# bno08x_module.net
KiCad netlist of a schematic drawn in Altium Designer
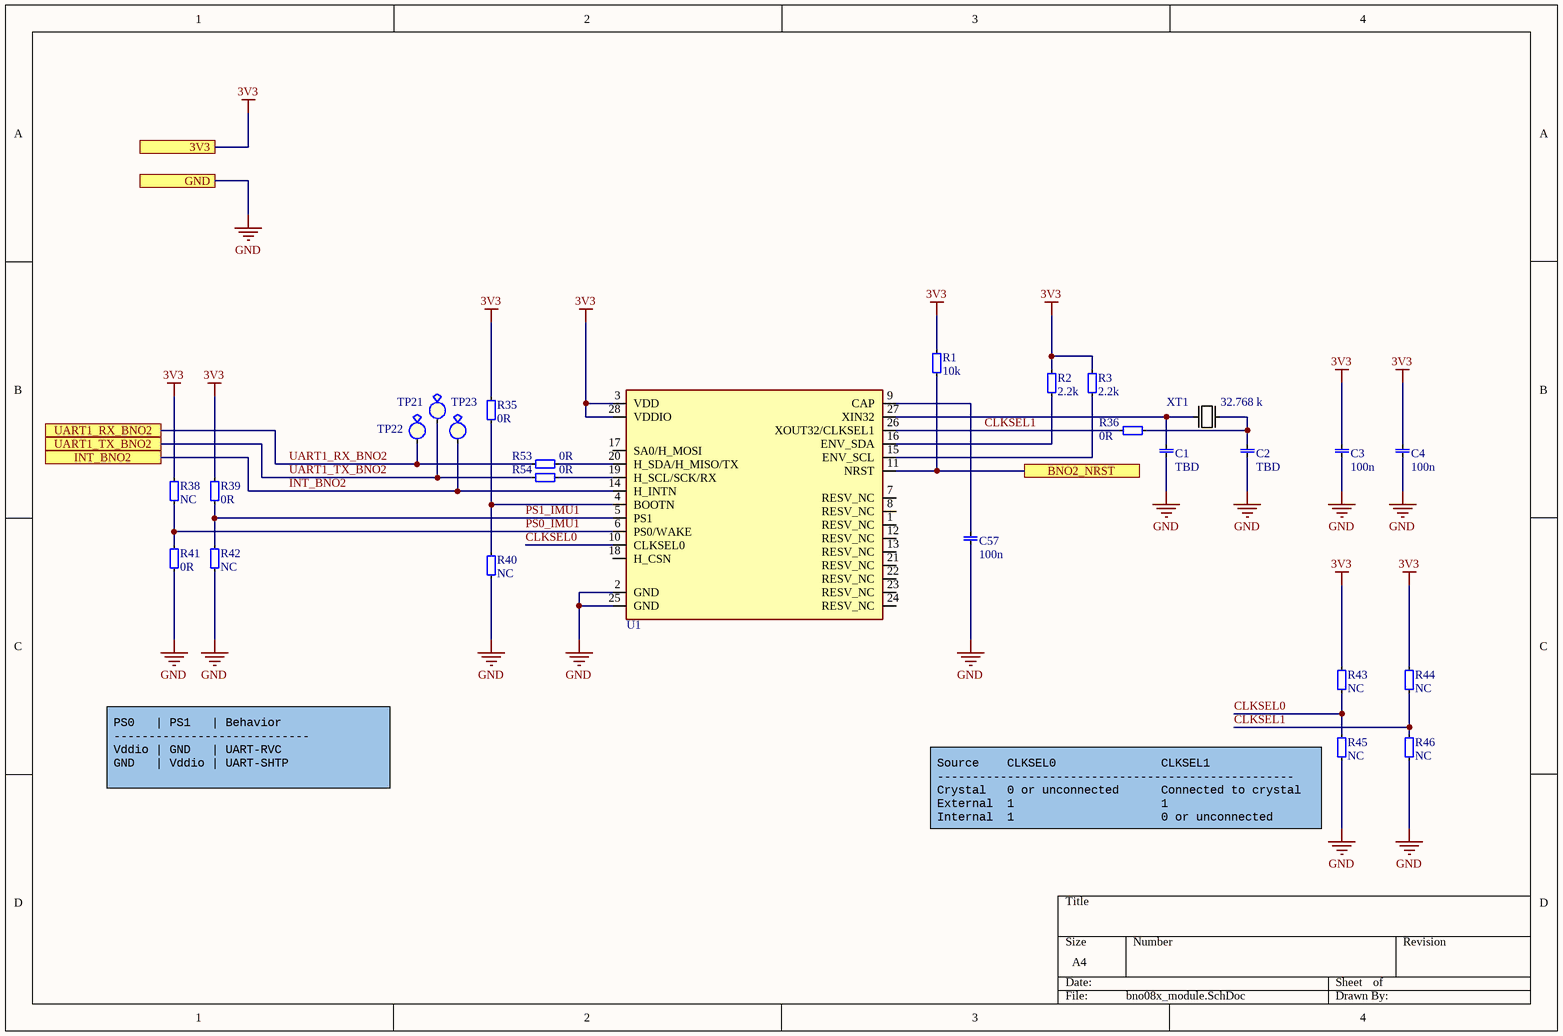
[diagram p0: bno08x_module.SchDoc]

(export (version "E")
  (design (tool "Eeschema 10.0.6"))
  (components
    (comp (ref "C1")
      (value "TBD")
      (footprint "0402 CAP")
      (fields (field (name "Comment") "0402 capacitor"))
      (libsource (lib "jclib") (part "0402 capacitor"))
    )
    (comp (ref "C2")
      (value "TBD")
      (footprint "0402 CAP")
      (fields (field (name "Comment") "0402 capacitor"))
      (libsource (lib "jclib") (part "0402 capacitor"))
    )
    (comp (ref "C3")
      (value "100n")
      (footprint "0402 CAP")
      (fields
        (field (name "MANUFACTURER PART NO") "GRM155R62A104KE14D")
        (field (name "Comment") "0402 capacitor")
      )
      (libsource (lib "jclib") (part "0402 capacitor"))
    )
    (comp (ref "C4")
      (value "100n")
      (footprint "0402 CAP")
      (fields
        (field (name "MANUFACTURER PART NO") "GRM155R62A104KE14D")
        (field (name "Comment") "0402 capacitor")
      )
      (libsource (lib "jclib") (part "0402 capacitor"))
    )
    (comp (ref "C57")
      (value "100n")
      (footprint "0402 CAP")
      (fields
        (field (name "MANUFACTURER PART NO") "GRM155R62A104KE14D")
        (field (name "Comment") "0402 capacitor")
      )
      (libsource (lib "jclib") (part "0402 capacitor"))
    )
    (comp (ref "R1")
      (value "10k")
      (footprint "0402 res")
      (fields
        (field (name "MANUFACTURER PART NO") "311-10.0KLRCT-ND")
        (field (name "Comment") "0402, resistor")
      )
      (libsource (lib "jclib") (part "0402, resistor"))
    )
    (comp (ref "R2")
      (value "2.2k")
      (footprint "0402 res")
      (fields
        (field (name "MANUFACTURER PART NO") "RC0402FR-072K2L")
        (field (name "Comment") "0402, resistor")
      )
      (libsource (lib "jclib") (part "0402, resistor"))
    )
    (comp (ref "R3")
      (value "2.2k")
      (footprint "0402 res")
      (fields
        (field (name "MANUFACTURER PART NO") "RC0402FR-072K2L")
        (field (name "Comment") "0402, resistor")
      )
      (libsource (lib "jclib") (part "0402, resistor"))
    )
    (comp (ref "R35")
      (value "0R")
      (footprint "0402 res")
      (fields
        (field (name "MANUFACTURER PART NO") "RMCF0402ZT0R00")
        (field (name "Comment") "0402, resistor")
      )
      (libsource (lib "jclib") (part "0402, resistor"))
    )
    (comp (ref "R36")
      (value "0R")
      (footprint "0402 res")
      (fields
        (field (name "MANUFACTURER PART NO") "RMCF0402ZT0R00")
        (field (name "Comment") "0402, resistor")
      )
      (libsource (lib "jclib") (part "0402, resistor"))
    )
    (comp (ref "R38")
      (value "NC")
      (footprint "0402 res")
      (fields (field (name "Comment") "0402, resistor"))
      (libsource (lib "jclib") (part "0402, resistor"))
    )
    (comp (ref "R39")
      (value "0R")
      (footprint "0402 res")
      (fields
        (field (name "MANUFACTURER PART NO") "RMCF0402ZT0R00")
        (field (name "Comment") "0402, resistor")
      )
      (libsource (lib "jclib") (part "0402, resistor"))
    )
    (comp (ref "R40")
      (value "NC")
      (footprint "0402 res")
      (fields (field (name "Comment") "0402, resistor"))
      (libsource (lib "jclib") (part "0402, resistor"))
    )
    (comp (ref "R41")
      (value "0R")
      (footprint "0402 res")
      (fields
        (field (name "MANUFACTURER PART NO") "RMCF0402ZT0R00")
        (field (name "Comment") "0402, resistor")
      )
      (libsource (lib "jclib") (part "0402, resistor"))
    )
    (comp (ref "R42")
      (value "NC")
      (footprint "0402 res")
      (fields (field (name "Comment") "0402, resistor"))
      (libsource (lib "jclib") (part "0402, resistor"))
    )
    (comp (ref "R43")
      (value "NC")
      (footprint "0402 res")
      (fields (field (name "Comment") "0402, resistor"))
      (libsource (lib "jclib") (part "0402, resistor"))
    )
    (comp (ref "R44")
      (value "NC")
      (footprint "0402 res")
      (fields (field (name "Comment") "0402, resistor"))
      (libsource (lib "jclib") (part "0402, resistor"))
    )
    (comp (ref "R45")
      (value "NC")
      (footprint "0402 res")
      (fields (field (name "Comment") "0402, resistor"))
      (libsource (lib "jclib") (part "0402, resistor"))
    )
    (comp (ref "R46")
      (value "NC")
      (footprint "0402 res")
      (fields (field (name "Comment") "0402, resistor"))
      (libsource (lib "jclib") (part "0402, resistor"))
    )
    (comp (ref "R53")
      (value "0R")
      (footprint "0402 res")
      (fields
        (field (name "MANUFACTURER PART NO") "RMCF0402ZT0R00")
        (field (name "Comment") "0402, resistor")
      )
      (libsource (lib "jclib") (part "0402, resistor"))
    )
    (comp (ref "R54")
      (value "0R")
      (footprint "0402 res")
      (fields
        (field (name "MANUFACTURER PART NO") "RMCF0402ZT0R00")
        (field (name "Comment") "0402, resistor")
      )
      (libsource (lib "jclib") (part "0402, resistor"))
    )
    (comp (ref "TP21")
      (value "Test Point")
      (footprint "TESTPOINT_SMD")
      (libsource (lib "jclib") (part "Test Point"))
    )
    (comp (ref "TP22")
      (value "Test Point")
      (footprint "TESTPOINT_SMD")
      (libsource (lib "jclib") (part "Test Point"))
    )
    (comp (ref "TP23")
      (value "Test Point")
      (footprint "TESTPOINT_SMD")
      (libsource (lib "jclib") (part "Test Point"))
    )
    (comp (ref "U1")
      (value "BNO08X")
      (footprint "LGA-28_2")
      (description "9-axis IMU")
      (fields (field (name "MANUFACTURER PART NO") "BNO085"))
      (libsource (lib "jclib") (part "BNO08X"))
    )
    (comp (ref "XT1")
      (value "32.768 k")
      (footprint "ECS-.327-12.5-39-TR")
      (fields
        (field (name "MANUFACTURER PART NO") "CC4V-T1A-32.768KHZ-9PF-20PPM-TA-QC")
        (field (name "Comment") "Crystal")
      )
      (libsource (lib "jclib") (part "Crystal"))
    )
  )
  (nets
    (net (code "1") (name "/BNO2_NRST") (class "Default")
      (node (ref "R1") (pin "0") (pinfunction "0_0") (pintype "passive"))
      (node (ref "U1") (pin "11") (pinfunction "NRST_11") (pintype "passive"))
    )
    (net (code "2") (name "/CLKSEL0") (class "Default")
      (node (ref "R43") (pin "1") (pinfunction "1_1") (pintype "passive"))
      (node (ref "R45") (pin "0") (pinfunction "0_0") (pintype "passive"))
      (node (ref "U1") (pin "10") (pinfunction "CLKSEL0_10") (pintype "passive"))
    )
    (net (code "3") (name "/CLKSEL1") (class "Default")
      (node (ref "R36") (pin "0") (pinfunction "0_0") (pintype "passive"))
      (node (ref "R44") (pin "1") (pinfunction "1_1") (pintype "passive"))
      (node (ref "R46") (pin "0") (pinfunction "0_0") (pintype "passive"))
      (node (ref "U1") (pin "26") (pinfunction "XOUT32/CLKSEL1_26") (pintype "passive"))
    )
    (net (code "4") (name "/INT_BNO2") (class "Default")
      (node (ref "TP23") (pin "0") (pinfunction "0_0") (pintype "passive"))
      (node (ref "U1") (pin "14") (pinfunction "H_INTN_14") (pintype "passive"))
    )
    (net (code "5") (name "/PS0_IMU1") (class "Default")
      (node (ref "R38") (pin "1") (pinfunction "1_1") (pintype "passive"))
      (node (ref "R41") (pin "0") (pinfunction "0_0") (pintype "passive"))
      (node (ref "U1") (pin "6") (pinfunction "PS0/WAKE_6") (pintype "passive"))
    )
    (net (code "6") (name "/PS1_IMU1") (class "Default")
      (node (ref "R39") (pin "1") (pinfunction "1_1") (pintype "passive"))
      (node (ref "R42") (pin "0") (pinfunction "0_0") (pintype "passive"))
      (node (ref "U1") (pin "5") (pinfunction "PS1_5") (pintype "passive"))
    )
    (net (code "7") (name "/UART1_RX_BNO2") (class "Default")
      (node (ref "R53") (pin "1") (pinfunction "1_1") (pintype "passive"))
      (node (ref "TP22") (pin "0") (pinfunction "0_0") (pintype "passive"))
    )
    (net (code "8") (name "/UART1_TX_BNO2") (class "Default")
      (node (ref "R54") (pin "1") (pinfunction "1_1") (pintype "passive"))
      (node (ref "TP21") (pin "0") (pinfunction "0_0") (pintype "passive"))
    )
    (net (code "9") (name "3V3") (class "Default")
      (node (ref "C3") (pin "1") (pinfunction "1_1") (pintype "passive"))
      (node (ref "C4") (pin "1") (pinfunction "1_1") (pintype "passive"))
      (node (ref "R1") (pin "1") (pinfunction "1_1") (pintype "passive"))
      (node (ref "R2") (pin "1") (pinfunction "1_1") (pintype "passive"))
      (node (ref "R3") (pin "1") (pinfunction "1_1") (pintype "passive"))
      (node (ref "R35") (pin "1") (pinfunction "1_1") (pintype "passive"))
      (node (ref "R38") (pin "0") (pinfunction "0_0") (pintype "passive"))
      (node (ref "R39") (pin "0") (pinfunction "0_0") (pintype "passive"))
      (node (ref "R43") (pin "0") (pinfunction "0_0") (pintype "passive"))
      (node (ref "R44") (pin "0") (pinfunction "0_0") (pintype "passive"))
      (node (ref "U1") (pin "28") (pinfunction "VDDIO_28") (pintype "passive"))
      (node (ref "U1") (pin "3") (pinfunction "VDD_3") (pintype "passive"))
    )
    (net (code "10") (name "GND") (class "Default")
      (node (ref "C1") (pin "0") (pinfunction "0_0") (pintype "passive"))
      (node (ref "C2") (pin "0") (pinfunction "0_0") (pintype "passive"))
      (node (ref "C3") (pin "0") (pinfunction "0_0") (pintype "passive"))
      (node (ref "C4") (pin "0") (pinfunction "0_0") (pintype "passive"))
      (node (ref "C57") (pin "0") (pinfunction "0_0") (pintype "passive"))
      (node (ref "R40") (pin "1") (pinfunction "1_1") (pintype "passive"))
      (node (ref "R41") (pin "1") (pinfunction "1_1") (pintype "passive"))
      (node (ref "R42") (pin "1") (pinfunction "1_1") (pintype "passive"))
      (node (ref "R45") (pin "1") (pinfunction "1_1") (pintype "passive"))
      (node (ref "R46") (pin "1") (pinfunction "1_1") (pintype "passive"))
      (node (ref "U1") (pin "2") (pinfunction "GND_2") (pintype "passive"))
      (node (ref "U1") (pin "25") (pinfunction "GND_25") (pintype "passive"))
    )
    (net (code "11") (name "Net-(C2-Pad1)") (class "Default")
      (node (ref "C2") (pin "1") (pinfunction "1_1") (pintype "passive"))
      (node (ref "R36") (pin "1") (pinfunction "1_1") (pintype "passive"))
      (node (ref "XT1") (pin "2") (pinfunction "2_2") (pintype "passive"))
    )
    (net (code "12") (name "Net-(U1-BOOTN)") (class "Default")
      (node (ref "R35") (pin "0") (pinfunction "0_0") (pintype "passive"))
      (node (ref "R40") (pin "0") (pinfunction "0_0") (pintype "passive"))
      (node (ref "U1") (pin "4") (pinfunction "BOOTN_4") (pintype "passive"))
    )
    (net (code "13") (name "Net-(U1-CAP)") (class "Default")
      (node (ref "C57") (pin "1") (pinfunction "1_1") (pintype "passive"))
      (node (ref "U1") (pin "9") (pinfunction "CAP_9") (pintype "passive"))
    )
    (net (code "14") (name "Net-(U1-ENV_SCL)") (class "Default")
      (node (ref "R3") (pin "0") (pinfunction "0_0") (pintype "passive"))
      (node (ref "U1") (pin "15") (pinfunction "ENV_SCL_15") (pintype "passive"))
    )
    (net (code "15") (name "Net-(U1-ENV_SDA)") (class "Default")
      (node (ref "R2") (pin "0") (pinfunction "0_0") (pintype "passive"))
      (node (ref "U1") (pin "16") (pinfunction "ENV_SDA_16") (pintype "passive"))
    )
    (net (code "16") (name "Net-(U1-H_SCL{slash}SCK{slash}RX)") (class "Default")
      (node (ref "R54") (pin "0") (pinfunction "0_0") (pintype "passive"))
      (node (ref "U1") (pin "19") (pinfunction "H_SCL/SCK/RX_19") (pintype "passive"))
    )
    (net (code "17") (name "Net-(U1-H_SDA{slash}H_MISO{slash}TX)") (class "Default")
      (node (ref "R53") (pin "0") (pinfunction "0_0") (pintype "passive"))
      (node (ref "U1") (pin "20") (pinfunction "H_SDA/H_MISO/TX_20") (pintype "passive"))
    )
    (net (code "18") (name "Net-(U1-XIN32)") (class "Default")
      (node (ref "C1") (pin "1") (pinfunction "1_1") (pintype "passive"))
      (node (ref "U1") (pin "27") (pinfunction "XIN32_27") (pintype "passive"))
      (node (ref "XT1") (pin "1") (pinfunction "1_1") (pintype "passive"))
    )
    (net (code "19") (name "unconnected-(U1-H_CSN-Pad18)") (class "Default")
      (node (ref "U1") (pin "18") (pinfunction "H_CSN_18") (pintype "passive"))
    )
    (net (code "20") (name "unconnected-(U1-RESV_NC-Pad1)") (class "Default")
      (node (ref "U1") (pin "1") (pinfunction "RESV_NC_1") (pintype "passive"))
    )
    (net (code "21") (name "unconnected-(U1-RESV_NC-Pad7)") (class "Default")
      (node (ref "U1") (pin "7") (pinfunction "RESV_NC_7") (pintype "passive"))
    )
    (net (code "22") (name "unconnected-(U1-RESV_NC-Pad8)") (class "Default")
      (node (ref "U1") (pin "8") (pinfunction "RESV_NC_8") (pintype "passive"))
    )
    (net (code "23") (name "unconnected-(U1-RESV_NC-Pad12)") (class "Default")
      (node (ref "U1") (pin "12") (pinfunction "RESV_NC_12") (pintype "passive"))
    )
    (net (code "24") (name "unconnected-(U1-RESV_NC-Pad13)") (class "Default")
      (node (ref "U1") (pin "13") (pinfunction "RESV_NC_13") (pintype "passive"))
    )
    (net (code "25") (name "unconnected-(U1-RESV_NC-Pad21)") (class "Default")
      (node (ref "U1") (pin "21") (pinfunction "RESV_NC_21") (pintype "passive"))
    )
    (net (code "26") (name "unconnected-(U1-RESV_NC-Pad22)") (class "Default")
      (node (ref "U1") (pin "22") (pinfunction "RESV_NC_22") (pintype "passive"))
    )
    (net (code "27") (name "unconnected-(U1-RESV_NC-Pad23)") (class "Default")
      (node (ref "U1") (pin "23") (pinfunction "RESV_NC_23") (pintype "passive"))
    )
    (net (code "28") (name "unconnected-(U1-RESV_NC-Pad24)") (class "Default")
      (node (ref "U1") (pin "24") (pinfunction "RESV_NC_24") (pintype "passive"))
    )
    (net (code "29") (name "unconnected-(U1-SA0{slash}H_MOSI-Pad17)") (class "Default")
      (node (ref "U1") (pin "17") (pinfunction "SA0/H_MOSI_17") (pintype "passive"))
    )
  )
)
